# Sch_esp32_kit.net
KiCad netlist of a schematic drawn in Altium Designer
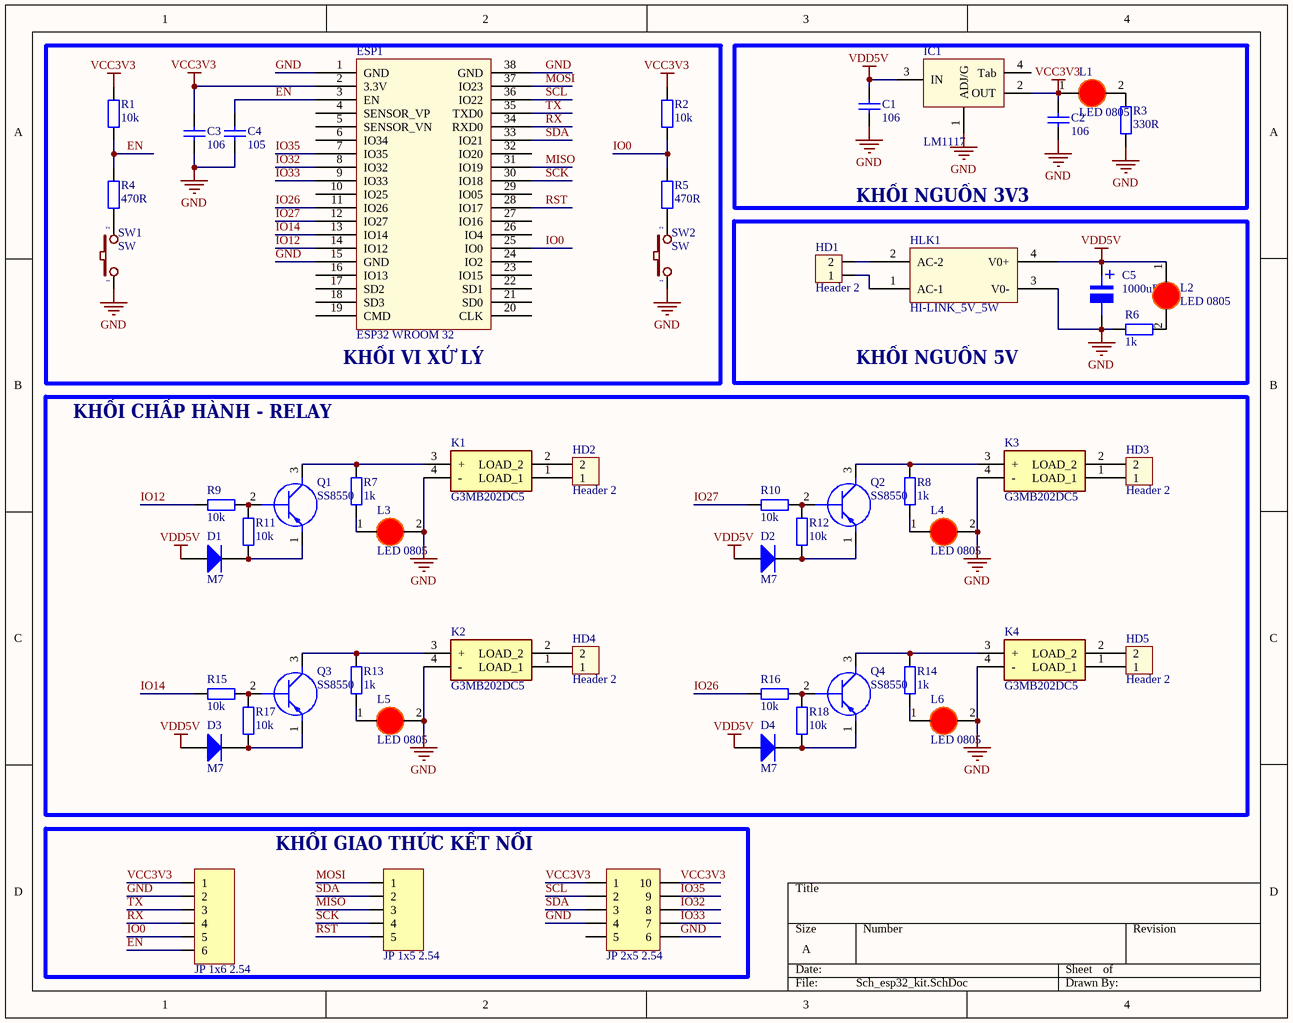
[diagram p0: Sch_esp32_kit.SchDoc]

(export (version "E")
  (design (tool "Eeschema 10.0.6"))
  (components
    (comp (ref "C1")
      (value "106")
      (footprint "tu 0603")
      (description "Dán")
      (libsource (lib "Tu dien") (part "Tu 0603 106 16V 20%"))
    )
    (comp (ref "C2")
      (value "106")
      (footprint "tu 0603")
      (description "Dán")
      (libsource (lib "Tu dien") (part "Tu 0603 106 16V 20%"))
    )
    (comp (ref "C3")
      (value "106")
      (footprint "tu 0603")
      (description "Dán")
      (libsource (lib "Tu dien") (part "Tu 0603 106 16V 20%"))
    )
    (comp (ref "C4")
      (value "105")
      (footprint "tu 0603")
      (description "Dán")
      (libsource (lib "Tu dien") (part "Tu 0603 105 50V 10%"))
    )
    (comp (ref "C5")
      (value "1000uF")
      (footprint "tu nhom 10 (G)")
      (description "Dán")
      (libsource (lib "Tu dien") (part "Tu Nhom 1000uF 10V"))
    )
    (comp (ref "D1")
      (value "M7")
      (footprint "DIODE SMA")
      (description "Dán")
      (libsource (lib "Diode") (part "Diode M7 ( 4007 )"))
    )
    (comp (ref "D2")
      (value "M7")
      (footprint "DIODE SMA")
      (description "Dán")
      (libsource (lib "Diode") (part "Diode M7 ( 4007 )"))
    )
    (comp (ref "D3")
      (value "M7")
      (footprint "DIODE SMA")
      (description "Dán")
      (libsource (lib "Diode") (part "Diode M7 ( 4007 )"))
    )
    (comp (ref "D4")
      (value "M7")
      (footprint "DIODE SMA")
      (description "Dán")
      (libsource (lib "Diode") (part "Diode M7 ( 4007 )"))
    )
    (comp (ref "ESP1")
      (value "ESP32 WROOM 32")
      (footprint "ESP32-WROOM-32D")
      (libsource (lib "IC") (part "ESP32 WROOM 32"))
    )
    (comp (ref "HD1")
      (value "Header 2")
      (footprint "HED2")
      (description "Header 2 (Green)")
      (libsource (lib "") (part "Hed2_1"))
    )
    (comp (ref "HD2")
      (value "Header 2")
      (footprint "HED2")
      (description "Header 2 (Green)")
      (libsource (lib "syhaunguyen") (part "Hed2"))
    )
    (comp (ref "HD3")
      (value "Header 2")
      (footprint "HED2")
      (description "Header 2 (Green)")
      (libsource (lib "syhaunguyen") (part "Hed2"))
    )
    (comp (ref "HD4")
      (value "Header 2")
      (footprint "HED2")
      (description "Header 2 (Green)")
      (libsource (lib "syhaunguyen") (part "Hed2"))
    )
    (comp (ref "HD5")
      (value "Header 2")
      (footprint "HED2")
      (description "Header 2 (Green)")
      (libsource (lib "syhaunguyen") (part "Hed2"))
    )
    (comp (ref "HLK1")
      (value "HI-LINK_5V_5W")
      (footprint "HLK10M05")
      (description "Integrated Circuit")
      (fields (field (name "MANUFACTURER_PART_NUMBER") "ams1117-3.3v"))
      (libsource (lib "test") (part "HI-LINK_5V_5W"))
    )
    (comp (ref "IC1")
      (value "LM1117")
      (footprint "SOT223-4N")
      (description "3v3")
      (libsource (lib "syhaunguyen") (part "LM1117"))
    )
    (comp (ref "JP1")
      (value "JP 1x6 2.54")
      (footprint "JP 1x6 DT")
      (description "Cắm")
      (libsource (lib "Jump") (part "JP 1x6 2.54 Duc Thang"))
    )
    (comp (ref "JP2")
      (value "JP 1x5 2.54")
      (footprint "JP 1x5 DT")
      (description "Cắm")
      (libsource (lib "Jump") (part "JP 1x5 2.54 Duc Thang"))
    )
    (comp (ref "JP3")
      (value "JP 2x5 2.54")
      (footprint "JP 2x5 DT")
      (description "Cắm")
      (libsource (lib "Jump") (part "JP 2x5 2.54 Duc Thang"))
    )
    (comp (ref "K1")
      (value "G3MB202DC5")
      (footprint "G3MC-201PL")
      (description "Relay or Contactor")
      (fields
        (field (name "MANUFACTURER_PART_NUMBER") "G3MB-202P-4 DC5")
        (field (name "MOUSER PART NUMBER") "653-G3MB-202P4DC5")
      )
      (libsource (lib "test") (part "G3MB-202P-DC5_1"))
    )
    (comp (ref "K2")
      (value "G3MB202DC5")
      (footprint "G3MC-201PL")
      (description "Relay or Contactor")
      (fields
        (field (name "MANUFACTURER_PART_NUMBER") "G3MB-202P-4 DC5")
        (field (name "MOUSER PART NUMBER") "653-G3MB-202P4DC5")
      )
      (libsource (lib "test") (part "G3MB-202P-DC5_1"))
    )
    (comp (ref "K3")
      (value "G3MB202DC5")
      (footprint "G3MC-201PL")
      (description "Relay or Contactor")
      (fields
        (field (name "MANUFACTURER_PART_NUMBER") "G3MB-202P-4 DC5")
        (field (name "MOUSER PART NUMBER") "653-G3MB-202P4DC5")
      )
      (libsource (lib "test") (part "G3MB-202P-DC5_1"))
    )
    (comp (ref "K4")
      (value "G3MB202DC5")
      (footprint "G3MC-201PL")
      (description "Relay or Contactor")
      (fields
        (field (name "MANUFACTURER_PART_NUMBER") "G3MB-202P-4 DC5")
        (field (name "MOUSER PART NUMBER") "653-G3MB-202P4DC5")
      )
      (libsource (lib "test") (part "G3MB-202P-DC5_1"))
    )
    (comp (ref "L1")
      (value "LED 0805")
      (footprint "LED-0805-Red")
      (description "Dán")
      (libsource (lib "Led") (part "LED 0805 Do"))
    )
    (comp (ref "L2")
      (value "LED 0805")
      (footprint "LED-0805-Red")
      (description "Dán")
      (libsource (lib "Led") (part "LED 0805 Do"))
    )
    (comp (ref "L3")
      (value "LED 0805")
      (footprint "LED-0805-Red")
      (description "Dán")
      (libsource (lib "Led") (part "LED 0805 Do"))
    )
    (comp (ref "L4")
      (value "LED 0805")
      (footprint "LED-0805-Red")
      (description "Dán")
      (libsource (lib "Led") (part "LED 0805 Do"))
    )
    (comp (ref "L5")
      (value "LED 0805")
      (footprint "LED-0805-Red")
      (description "Dán")
      (libsource (lib "Led") (part "LED 0805 Do"))
    )
    (comp (ref "L6")
      (value "LED 0805")
      (footprint "LED-0805-Red")
      (description "Dán")
      (libsource (lib "Led") (part "LED 0805 Do"))
    )
    (comp (ref "Q1")
      (value "SS8550")
      (footprint "SamacSys:SS8550")
      (description "Transistor BJT PNP")
      (libsource (lib "test") (part "SS8550"))
    )
    (comp (ref "Q2")
      (value "SS8550")
      (footprint "SamacSys:SS8550")
      (description "Transistor BJT PNP")
      (libsource (lib "test") (part "SS8550"))
    )
    (comp (ref "Q3")
      (value "SS8550")
      (footprint "SamacSys:SS8550")
      (description "Transistor BJT PNP")
      (libsource (lib "test") (part "SS8550"))
    )
    (comp (ref "Q4")
      (value "SS8550")
      (footprint "SamacSys:SS8550")
      (description "Transistor BJT PNP")
      (libsource (lib "test") (part "SS8550"))
    )
    (comp (ref "R1")
      (value "10k")
      (footprint "tro smd 0603")
      (description "Dán")
      (libsource (lib "Dien Tro") (part "Tro 0603 5% 10k"))
    )
    (comp (ref "R2")
      (value "10k")
      (footprint "tro smd 0603")
      (description "Dán")
      (libsource (lib "Dien Tro") (part "Tro 0603 5% 10k"))
    )
    (comp (ref "R3")
      (value "330R")
      (footprint "tro smd 0603")
      (description "Dán")
      (libsource (lib "Dien Tro") (part "Tro 0603 5% 330R"))
    )
    (comp (ref "R4")
      (value "470R")
      (footprint "tro smd 0603")
      (description "Dán")
      (libsource (lib "Dien Tro") (part "Tro 0603 5% 470R"))
    )
    (comp (ref "R5")
      (value "470R")
      (footprint "tro smd 0603")
      (description "Dán")
      (libsource (lib "Dien Tro") (part "Tro 0603 5% 470R"))
    )
    (comp (ref "R6")
      (value "1k")
      (footprint "tro smd 0603")
      (description "Dán")
      (libsource (lib "Dien Tro") (part "Tro 0603 5% 1k"))
    )
    (comp (ref "R7")
      (value "1k")
      (footprint "tro smd 0603")
      (description "Dán")
      (libsource (lib "Dien Tro") (part "Tro 0603 5% 1k"))
    )
    (comp (ref "R8")
      (value "1k")
      (footprint "tro smd 0603")
      (description "Dán")
      (libsource (lib "Dien Tro") (part "Tro 0603 5% 1k"))
    )
    (comp (ref "R9")
      (value "10k")
      (footprint "tro smd 0603")
      (description "Dán")
      (libsource (lib "Dien Tro") (part "Tro 0603 5% 10k"))
    )
    (comp (ref "R10")
      (value "10k")
      (footprint "tro smd 0603")
      (description "Dán")
      (libsource (lib "Dien Tro") (part "Tro 0603 5% 10k"))
    )
    (comp (ref "R11")
      (value "10k")
      (footprint "tro smd 0603")
      (description "Dán")
      (libsource (lib "Dien Tro") (part "Tro 0603 5% 10k"))
    )
    (comp (ref "R12")
      (value "10k")
      (footprint "tro smd 0603")
      (description "Dán")
      (libsource (lib "Dien Tro") (part "Tro 0603 5% 10k"))
    )
    (comp (ref "R13")
      (value "1k")
      (footprint "tro smd 0603")
      (description "Dán")
      (libsource (lib "Dien Tro") (part "Tro 0603 5% 1k"))
    )
    (comp (ref "R14")
      (value "1k")
      (footprint "tro smd 0603")
      (description "Dán")
      (libsource (lib "Dien Tro") (part "Tro 0603 5% 1k"))
    )
    (comp (ref "R15")
      (value "10k")
      (footprint "tro smd 0603")
      (description "Dán")
      (libsource (lib "Dien Tro") (part "Tro 0603 5% 10k"))
    )
    (comp (ref "R16")
      (value "10k")
      (footprint "tro smd 0603")
      (description "Dán")
      (libsource (lib "Dien Tro") (part "Tro 0603 5% 10k"))
    )
    (comp (ref "R17")
      (value "10k")
      (footprint "tro smd 0603")
      (description "Dán")
      (libsource (lib "Dien Tro") (part "Tro 0603 5% 10k"))
    )
    (comp (ref "R18")
      (value "10k")
      (footprint "tro smd 0603")
      (description "Dán")
      (libsource (lib "Dien Tro") (part "Tro 0603 5% 10k"))
    )
    (comp (ref "SW1")
      (value "SW")
      (footprint "SW1-SMD")
      (description "Switch button 2 pin")
      (libsource (lib "TechMT.VN_Lib_Project v2") (part "SW2"))
    )
    (comp (ref "SW2")
      (value "SW")
      (footprint "SW1-SMD")
      (description "Switch button 2 pin")
      (libsource (lib "TechMT.VN_Lib_Project v2") (part "SW2"))
    )
  )
  (nets
    (net (code "1") (name "/EN") (class "Default")
      (node (ref "C4") (pin "1") (pinfunction "1_1") (pintype "passive"))
      (node (ref "ESP1") (pin "3") (pinfunction "EN_3") (pintype "passive"))
      (node (ref "JP1") (pin "6") (pinfunction "6_6") (pintype "passive"))
      (node (ref "R1") (pin "1") (pinfunction "1_1") (pintype "passive"))
      (node (ref "R4") (pin "2") (pinfunction "2_2") (pintype "passive"))
    )
    (net (code "2") (name "/IO0") (class "Default")
      (node (ref "ESP1") (pin "25") (pinfunction "IO0_25") (pintype "passive"))
      (node (ref "JP1") (pin "5") (pinfunction "5_5") (pintype "passive"))
      (node (ref "R2") (pin "1") (pinfunction "1_1") (pintype "passive"))
      (node (ref "R5") (pin "2") (pinfunction "2_2") (pintype "passive"))
    )
    (net (code "3") (name "/IO12") (class "Default")
      (node (ref "ESP1") (pin "14") (pinfunction "IO12_14") (pintype "passive"))
      (node (ref "R9") (pin "2") (pinfunction "2_2") (pintype "passive"))
    )
    (net (code "4") (name "/IO14") (class "Default")
      (node (ref "ESP1") (pin "13") (pinfunction "IO14_13") (pintype "passive"))
      (node (ref "R15") (pin "2") (pinfunction "2_2") (pintype "passive"))
    )
    (net (code "5") (name "/IO26") (class "Default")
      (node (ref "ESP1") (pin "11") (pinfunction "IO26_11") (pintype "passive"))
      (node (ref "R16") (pin "2") (pinfunction "2_2") (pintype "passive"))
    )
    (net (code "6") (name "/IO27") (class "Default")
      (node (ref "ESP1") (pin "12") (pinfunction "IO27_12") (pintype "passive"))
      (node (ref "R10") (pin "2") (pinfunction "2_2") (pintype "passive"))
    )
    (net (code "7") (name "/IO32") (class "Default")
      (node (ref "ESP1") (pin "8") (pinfunction "IO32_8") (pintype "passive"))
      (node (ref "JP3") (pin "8") (pinfunction "8_8") (pintype "passive"))
    )
    (net (code "8") (name "/IO33") (class "Default")
      (node (ref "ESP1") (pin "9") (pinfunction "IO33_9") (pintype "passive"))
      (node (ref "JP3") (pin "7") (pinfunction "7_7") (pintype "passive"))
    )
    (net (code "9") (name "/IO35") (class "Default")
      (node (ref "ESP1") (pin "7") (pinfunction "IO35_7") (pintype "passive"))
      (node (ref "JP3") (pin "9") (pinfunction "9_9") (pintype "passive"))
    )
    (net (code "10") (name "/MISO") (class "Default")
      (node (ref "ESP1") (pin "31") (pinfunction "IO19_31") (pintype "passive"))
      (node (ref "JP2") (pin "3") (pinfunction "3_3") (pintype "passive"))
    )
    (net (code "11") (name "/MOSI") (class "Default")
      (node (ref "ESP1") (pin "37") (pinfunction "IO23_37") (pintype "passive"))
      (node (ref "JP2") (pin "1") (pinfunction "1_1") (pintype "passive"))
    )
    (net (code "12") (name "/RST") (class "Default")
      (node (ref "ESP1") (pin "28") (pinfunction "IO17_28") (pintype "passive"))
      (node (ref "JP2") (pin "5") (pinfunction "5_5") (pintype "passive"))
    )
    (net (code "13") (name "/RX") (class "Default")
      (node (ref "ESP1") (pin "34") (pinfunction "RXD0_34") (pintype "passive"))
      (node (ref "JP1") (pin "4") (pinfunction "4_4") (pintype "passive"))
    )
    (net (code "14") (name "/SCK") (class "Default")
      (node (ref "ESP1") (pin "30") (pinfunction "IO18_30") (pintype "passive"))
      (node (ref "JP2") (pin "4") (pinfunction "4_4") (pintype "passive"))
    )
    (net (code "15") (name "/SCL") (class "Default")
      (node (ref "ESP1") (pin "36") (pinfunction "IO22_36") (pintype "passive"))
      (node (ref "JP3") (pin "2") (pinfunction "2_2") (pintype "passive"))
    )
    (net (code "16") (name "/SDA") (class "Default")
      (node (ref "ESP1") (pin "33") (pinfunction "IO21_33") (pintype "passive"))
      (node (ref "JP2") (pin "2") (pinfunction "2_2") (pintype "passive"))
      (node (ref "JP3") (pin "3") (pinfunction "3_3") (pintype "passive"))
    )
    (net (code "17") (name "/TX") (class "Default")
      (node (ref "ESP1") (pin "35") (pinfunction "TXD0_35") (pintype "passive"))
      (node (ref "JP1") (pin "3") (pinfunction "3_3") (pintype "passive"))
    )
    (net (code "18") (name "GND") (class "Default")
      (node (ref "C1") (pin "2") (pinfunction "2_2") (pintype "passive"))
      (node (ref "C2") (pin "2") (pinfunction "2_2") (pintype "passive"))
      (node (ref "C3") (pin "2") (pinfunction "2_2") (pintype "passive"))
      (node (ref "C4") (pin "2") (pinfunction "2_2") (pintype "passive"))
      (node (ref "C5") (pin "2") (pinfunction "2_2") (pintype "passive"))
      (node (ref "ESP1") (pin "1") (pinfunction "GND_1") (pintype "passive"))
      (node (ref "ESP1") (pin "15") (pinfunction "GND_15") (pintype "passive"))
      (node (ref "ESP1") (pin "38") (pinfunction "GND_38") (pintype "passive"))
      (node (ref "HLK1") (pin "3") (pinfunction "V0-_3") (pintype "passive"))
      (node (ref "IC1") (pin "1") (pinfunction "ADJ/G_1") (pintype "passive"))
      (node (ref "JP1") (pin "2") (pinfunction "2_2") (pintype "passive"))
      (node (ref "JP3") (pin "4") (pinfunction "4_4") (pintype "passive"))
      (node (ref "JP3") (pin "6") (pinfunction "6_6") (pintype "passive"))
      (node (ref "K1") (pin "4") (pinfunction "-_4") (pintype "passive"))
      (node (ref "K2") (pin "4") (pinfunction "-_4") (pintype "passive"))
      (node (ref "K3") (pin "4") (pinfunction "-_4") (pintype "passive"))
      (node (ref "K4") (pin "4") (pinfunction "-_4") (pintype "passive"))
      (node (ref "L3") (pin "2") (pinfunction "K_2") (pintype "passive"))
      (node (ref "L4") (pin "2") (pinfunction "K_2") (pintype "passive"))
      (node (ref "L5") (pin "2") (pinfunction "K_2") (pintype "passive"))
      (node (ref "L6") (pin "2") (pinfunction "K_2") (pintype "passive"))
      (node (ref "R3") (pin "1") (pinfunction "1_1") (pintype "passive"))
      (node (ref "R6") (pin "1") (pinfunction "1_1") (pintype "passive"))
      (node (ref "SW1") (pin "1") (pinfunction "1_1") (pintype "passive"))
      (node (ref "SW2") (pin "1") (pinfunction "1_1") (pintype "passive"))
    )
    (net (code "19") (name "Net-(D1-K)") (class "Default")
      (node (ref "D1") (pin "2") (pinfunction "K_2") (pintype "passive"))
      (node (ref "Q1") (pin "1") (pinfunction "E_1") (pintype "passive"))
      (node (ref "R11") (pin "1") (pinfunction "1_1") (pintype "passive"))
    )
    (net (code "20") (name "Net-(D2-K)") (class "Default")
      (node (ref "D2") (pin "2") (pinfunction "K_2") (pintype "passive"))
      (node (ref "Q2") (pin "1") (pinfunction "E_1") (pintype "passive"))
      (node (ref "R12") (pin "1") (pinfunction "1_1") (pintype "passive"))
    )
    (net (code "21") (name "Net-(D3-K)") (class "Default")
      (node (ref "D3") (pin "2") (pinfunction "K_2") (pintype "passive"))
      (node (ref "Q3") (pin "1") (pinfunction "E_1") (pintype "passive"))
      (node (ref "R17") (pin "1") (pinfunction "1_1") (pintype "passive"))
    )
    (net (code "22") (name "Net-(D4-K)") (class "Default")
      (node (ref "D4") (pin "2") (pinfunction "K_2") (pintype "passive"))
      (node (ref "Q4") (pin "1") (pinfunction "E_1") (pintype "passive"))
      (node (ref "R18") (pin "1") (pinfunction "1_1") (pintype "passive"))
    )
    (net (code "23") (name "Net-(HLK1-AC-1)") (class "Default")
      (node (ref "HD1") (pin "1") (pinfunction "1_1") (pintype "passive"))
      (node (ref "HLK1") (pin "1") (pinfunction "AC-1_1") (pintype "passive"))
    )
    (net (code "24") (name "Net-(HLK1-AC-2)") (class "Default")
      (node (ref "HD1") (pin "2") (pinfunction "2_2") (pintype "passive"))
      (node (ref "HLK1") (pin "2") (pinfunction "AC-2_2") (pintype "passive"))
    )
    (net (code "25") (name "Net-(K1-+)") (class "Default")
      (node (ref "K1") (pin "3") (pinfunction "+_3") (pintype "passive"))
      (node (ref "Q1") (pin "3") (pinfunction "C_3") (pintype "passive"))
      (node (ref "R7") (pin "2") (pinfunction "2_2") (pintype "passive"))
    )
    (net (code "26") (name "Net-(K1-LOAD_1)") (class "Default")
      (node (ref "HD2") (pin "1") (pinfunction "1_1") (pintype "passive"))
      (node (ref "K1") (pin "1") (pinfunction "LOAD_1_1") (pintype "passive"))
    )
    (net (code "27") (name "Net-(K1-LOAD_2)") (class "Default")
      (node (ref "HD2") (pin "2") (pinfunction "2_2") (pintype "passive"))
      (node (ref "K1") (pin "2") (pinfunction "LOAD_2_2") (pintype "passive"))
    )
    (net (code "28") (name "Net-(K2-+)") (class "Default")
      (node (ref "K2") (pin "3") (pinfunction "+_3") (pintype "passive"))
      (node (ref "Q3") (pin "3") (pinfunction "C_3") (pintype "passive"))
      (node (ref "R13") (pin "2") (pinfunction "2_2") (pintype "passive"))
    )
    (net (code "29") (name "Net-(K2-LOAD_1)") (class "Default")
      (node (ref "HD4") (pin "1") (pinfunction "1_1") (pintype "passive"))
      (node (ref "K2") (pin "1") (pinfunction "LOAD_1_1") (pintype "passive"))
    )
    (net (code "30") (name "Net-(K2-LOAD_2)") (class "Default")
      (node (ref "HD4") (pin "2") (pinfunction "2_2") (pintype "passive"))
      (node (ref "K2") (pin "2") (pinfunction "LOAD_2_2") (pintype "passive"))
    )
    (net (code "31") (name "Net-(K3-+)") (class "Default")
      (node (ref "K3") (pin "3") (pinfunction "+_3") (pintype "passive"))
      (node (ref "Q2") (pin "3") (pinfunction "C_3") (pintype "passive"))
      (node (ref "R8") (pin "2") (pinfunction "2_2") (pintype "passive"))
    )
    (net (code "32") (name "Net-(K3-LOAD_1)") (class "Default")
      (node (ref "HD3") (pin "1") (pinfunction "1_1") (pintype "passive"))
      (node (ref "K3") (pin "1") (pinfunction "LOAD_1_1") (pintype "passive"))
    )
    (net (code "33") (name "Net-(K3-LOAD_2)") (class "Default")
      (node (ref "HD3") (pin "2") (pinfunction "2_2") (pintype "passive"))
      (node (ref "K3") (pin "2") (pinfunction "LOAD_2_2") (pintype "passive"))
    )
    (net (code "34") (name "Net-(K4-+)") (class "Default")
      (node (ref "K4") (pin "3") (pinfunction "+_3") (pintype "passive"))
      (node (ref "Q4") (pin "3") (pinfunction "C_3") (pintype "passive"))
      (node (ref "R14") (pin "2") (pinfunction "2_2") (pintype "passive"))
    )
    (net (code "35") (name "Net-(K4-LOAD_1)") (class "Default")
      (node (ref "HD5") (pin "1") (pinfunction "1_1") (pintype "passive"))
      (node (ref "K4") (pin "1") (pinfunction "LOAD_1_1") (pintype "passive"))
    )
    (net (code "36") (name "Net-(K4-LOAD_2)") (class "Default")
      (node (ref "HD5") (pin "2") (pinfunction "2_2") (pintype "passive"))
      (node (ref "K4") (pin "2") (pinfunction "LOAD_2_2") (pintype "passive"))
    )
    (net (code "37") (name "Net-(L1-K)") (class "Default")
      (node (ref "L1") (pin "2") (pinfunction "K_2") (pintype "passive"))
      (node (ref "R3") (pin "2") (pinfunction "2_2") (pintype "passive"))
    )
    (net (code "38") (name "Net-(L2-K)") (class "Default")
      (node (ref "L2") (pin "2") (pinfunction "K_2") (pintype "passive"))
      (node (ref "R6") (pin "2") (pinfunction "2_2") (pintype "passive"))
    )
    (net (code "39") (name "Net-(L3-A)") (class "Default")
      (node (ref "L3") (pin "1") (pinfunction "A_1") (pintype "passive"))
      (node (ref "R7") (pin "1") (pinfunction "1_1") (pintype "passive"))
    )
    (net (code "40") (name "Net-(L4-A)") (class "Default")
      (node (ref "L4") (pin "1") (pinfunction "A_1") (pintype "passive"))
      (node (ref "R8") (pin "1") (pinfunction "1_1") (pintype "passive"))
    )
    (net (code "41") (name "Net-(L5-A)") (class "Default")
      (node (ref "L5") (pin "1") (pinfunction "A_1") (pintype "passive"))
      (node (ref "R13") (pin "1") (pinfunction "1_1") (pintype "passive"))
    )
    (net (code "42") (name "Net-(L6-A)") (class "Default")
      (node (ref "L6") (pin "1") (pinfunction "A_1") (pintype "passive"))
      (node (ref "R14") (pin "1") (pinfunction "1_1") (pintype "passive"))
    )
    (net (code "43") (name "Net-(Q1-B)") (class "Default")
      (node (ref "Q1") (pin "2") (pinfunction "B_2") (pintype "passive"))
      (node (ref "R11") (pin "2") (pinfunction "2_2") (pintype "passive"))
      (node (ref "R9") (pin "1") (pinfunction "1_1") (pintype "passive"))
    )
    (net (code "44") (name "Net-(Q2-B)") (class "Default")
      (node (ref "Q2") (pin "2") (pinfunction "B_2") (pintype "passive"))
      (node (ref "R10") (pin "1") (pinfunction "1_1") (pintype "passive"))
      (node (ref "R12") (pin "2") (pinfunction "2_2") (pintype "passive"))
    )
    (net (code "45") (name "Net-(Q3-B)") (class "Default")
      (node (ref "Q3") (pin "2") (pinfunction "B_2") (pintype "passive"))
      (node (ref "R15") (pin "1") (pinfunction "1_1") (pintype "passive"))
      (node (ref "R17") (pin "2") (pinfunction "2_2") (pintype "passive"))
    )
    (net (code "46") (name "Net-(Q4-B)") (class "Default")
      (node (ref "Q4") (pin "2") (pinfunction "B_2") (pintype "passive"))
      (node (ref "R16") (pin "1") (pinfunction "1_1") (pintype "passive"))
      (node (ref "R18") (pin "2") (pinfunction "2_2") (pintype "passive"))
    )
    (net (code "47") (name "Net-(R4-Pad1)") (class "Default")
      (node (ref "R4") (pin "1") (pinfunction "1_1") (pintype "passive"))
      (node (ref "SW1") (pin "2") (pinfunction "2_2") (pintype "passive"))
    )
    (net (code "48") (name "Net-(R5-Pad1)") (class "Default")
      (node (ref "R5") (pin "1") (pinfunction "1_1") (pintype "passive"))
      (node (ref "SW2") (pin "2") (pinfunction "2_2") (pintype "passive"))
    )
    (net (code "49") (name "VCC3V3") (class "Default")
      (node (ref "C2") (pin "1") (pinfunction "1_1") (pintype "passive"))
      (node (ref "C3") (pin "1") (pinfunction "1_1") (pintype "passive"))
      (node (ref "ESP1") (pin "2") (pinfunction "3.3V_2") (pintype "passive"))
      (node (ref "IC1") (pin "2") (pinfunction "OUT_2") (pintype "passive"))
      (node (ref "JP1") (pin "1") (pinfunction "1_1") (pintype "passive"))
      (node (ref "JP3") (pin "1") (pinfunction "1_1") (pintype "passive"))
      (node (ref "JP3") (pin "10") (pinfunction "10_10") (pintype "passive"))
      (node (ref "L1") (pin "1") (pinfunction "A_1") (pintype "passive"))
      (node (ref "R1") (pin "2") (pinfunction "2_2") (pintype "passive"))
      (node (ref "R2") (pin "2") (pinfunction "2_2") (pintype "passive"))
    )
    (net (code "50") (name "VDD5V") (class "Default")
      (node (ref "C1") (pin "1") (pinfunction "1_1") (pintype "passive"))
      (node (ref "C5") (pin "1") (pinfunction "1_1") (pintype "passive"))
      (node (ref "D1") (pin "1") (pinfunction "A_1") (pintype "passive"))
      (node (ref "D2") (pin "1") (pinfunction "A_1") (pintype "passive"))
      (node (ref "D3") (pin "1") (pinfunction "A_1") (pintype "passive"))
      (node (ref "D4") (pin "1") (pinfunction "A_1") (pintype "passive"))
      (node (ref "HLK1") (pin "4") (pinfunction "V0+_4") (pintype "passive"))
      (node (ref "IC1") (pin "3") (pinfunction "IN_3") (pintype "passive"))
      (node (ref "L2") (pin "1") (pinfunction "A_1") (pintype "passive"))
    )
    (net (code "51") (name "unconnected-(ESP1-CLK-Pad20)") (class "Default")
      (node (ref "ESP1") (pin "20") (pinfunction "CLK_20") (pintype "passive"))
    )
    (net (code "52") (name "unconnected-(ESP1-CMD-Pad19)") (class "Default")
      (node (ref "ESP1") (pin "19") (pinfunction "CMD_19") (pintype "passive"))
    )
    (net (code "53") (name "unconnected-(ESP1-IO2-Pad24)") (class "Default")
      (node (ref "ESP1") (pin "24") (pinfunction "IO2_24") (pintype "passive"))
    )
    (net (code "54") (name "unconnected-(ESP1-IO4-Pad26)") (class "Default")
      (node (ref "ESP1") (pin "26") (pinfunction "IO4_26") (pintype "passive"))
    )
    (net (code "55") (name "unconnected-(ESP1-IO05-Pad29)") (class "Default")
      (node (ref "ESP1") (pin "29") (pinfunction "IO05_29") (pintype "passive"))
    )
    (net (code "56") (name "unconnected-(ESP1-IO13-Pad16)") (class "Default")
      (node (ref "ESP1") (pin "16") (pinfunction "IO13_16") (pintype "passive"))
    )
    (net (code "57") (name "unconnected-(ESP1-IO15-Pad23)") (class "Default")
      (node (ref "ESP1") (pin "23") (pinfunction "IO15_23") (pintype "passive"))
    )
    (net (code "58") (name "unconnected-(ESP1-IO16-Pad27)") (class "Default")
      (node (ref "ESP1") (pin "27") (pinfunction "IO16_27") (pintype "passive"))
    )
    (net (code "59") (name "unconnected-(ESP1-IO20-Pad32)") (class "Default")
      (node (ref "ESP1") (pin "32") (pinfunction "IO20_32") (pintype "passive"))
    )
    (net (code "60") (name "unconnected-(ESP1-IO25-Pad10)") (class "Default")
      (node (ref "ESP1") (pin "10") (pinfunction "IO25_10") (pintype "passive"))
    )
    (net (code "61") (name "unconnected-(ESP1-IO34-Pad6)") (class "Default")
      (node (ref "ESP1") (pin "6") (pinfunction "IO34_6") (pintype "passive"))
    )
    (net (code "62") (name "unconnected-(ESP1-SD0-Pad21)") (class "Default")
      (node (ref "ESP1") (pin "21") (pinfunction "SD0_21") (pintype "passive"))
    )
    (net (code "63") (name "unconnected-(ESP1-SD1-Pad22)") (class "Default")
      (node (ref "ESP1") (pin "22") (pinfunction "SD1_22") (pintype "passive"))
    )
    (net (code "64") (name "unconnected-(ESP1-SD2-Pad17)") (class "Default")
      (node (ref "ESP1") (pin "17") (pinfunction "SD2_17") (pintype "passive"))
    )
    (net (code "65") (name "unconnected-(ESP1-SD3-Pad18)") (class "Default")
      (node (ref "ESP1") (pin "18") (pinfunction "SD3_18") (pintype "passive"))
    )
    (net (code "66") (name "unconnected-(ESP1-SENSOR_VN-Pad5)") (class "Default")
      (node (ref "ESP1") (pin "5") (pinfunction "SENSOR_VN_5") (pintype "passive"))
    )
    (net (code "67") (name "unconnected-(ESP1-SENSOR_VP-Pad4)") (class "Default")
      (node (ref "ESP1") (pin "4") (pinfunction "SENSOR_VP_4") (pintype "passive"))
    )
    (net (code "68") (name "unconnected-(IC1-Tab-Pad4)") (class "Default")
      (node (ref "IC1") (pin "4") (pinfunction "Tab_4") (pintype "passive"))
    )
    (net (code "69") (name "unconnected-(JP3-Pad5)") (class "Default")
      (node (ref "JP3") (pin "5") (pinfunction "5_5") (pintype "passive"))
    )
  )
)
